# pcb_inverter.net
KiCad netlist of a schematic drawn in EAGLE
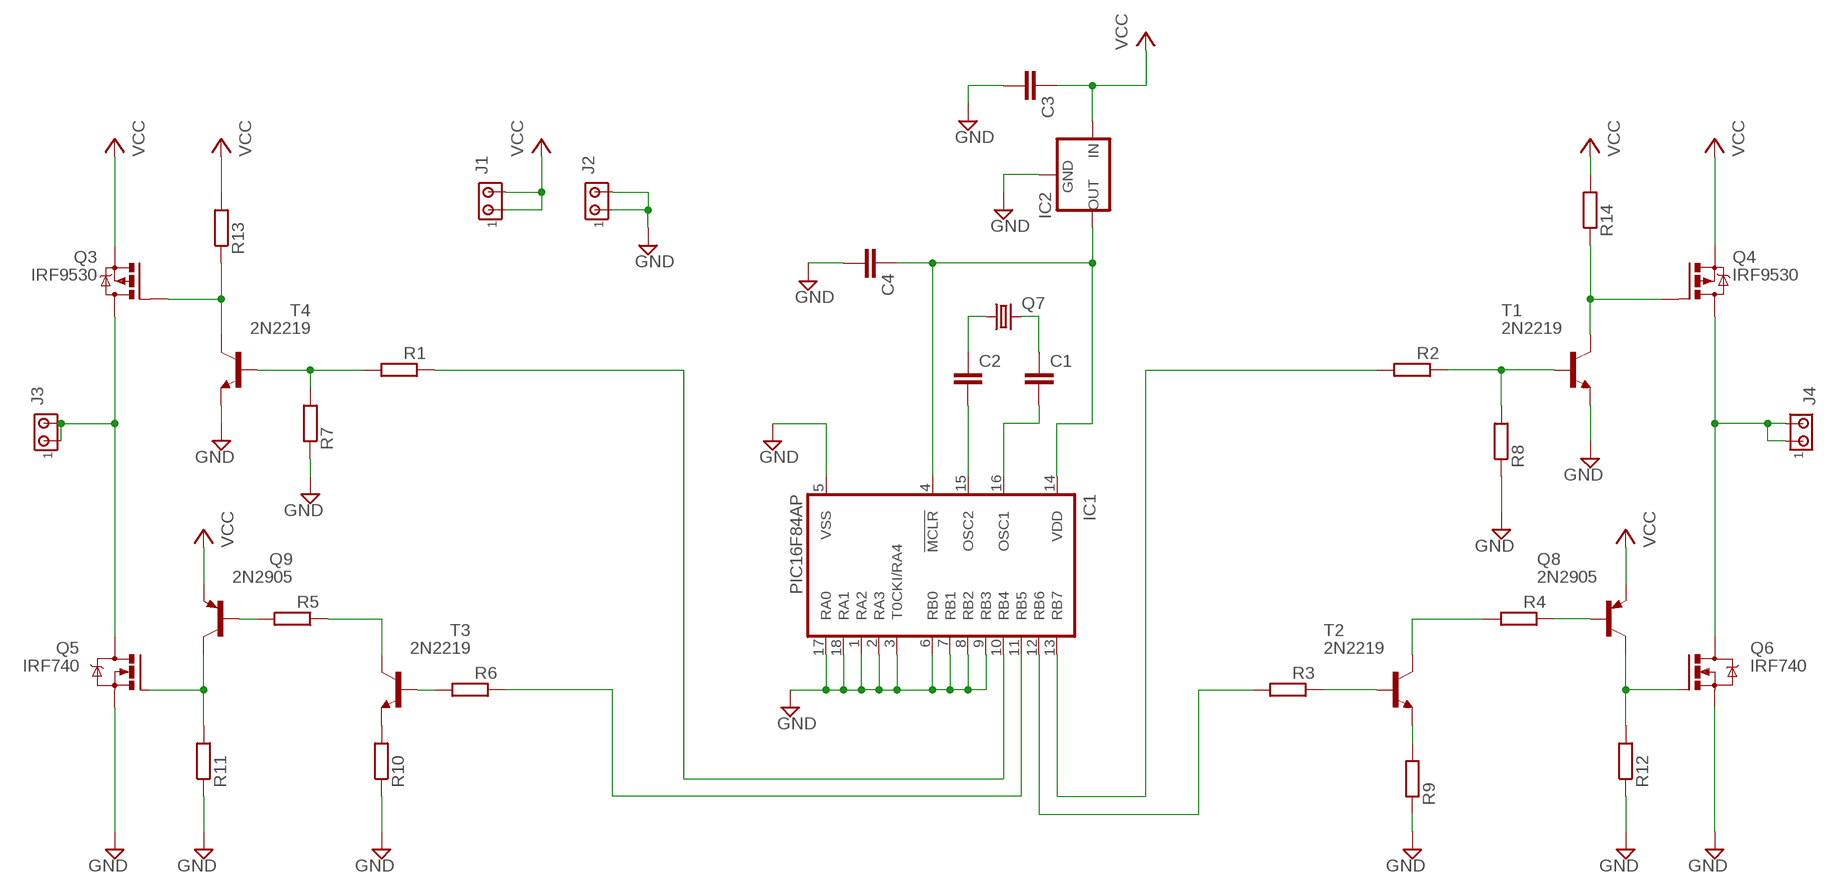
[diagram p0: schematic, sheet 1]

(export (version "E")
  (design (tool "Eeschema 10.0.6"))
  (components
    (comp (ref "C1")
      (value "C2.5/5")
      (footprint "eagle-import:C2.5-5")
      (libsource (lib "eagle-import") (part "C2.5/5"))
    )
    (comp (ref "C2")
      (value "C2.5/5")
      (footprint "eagle-import:C2.5-5")
      (libsource (lib "eagle-import") (part "C2.5/5"))
    )
    (comp (ref "C3")
      (value "C2.5/5")
      (footprint "eagle-import:C2.5-5")
      (libsource (lib "eagle-import") (part "C2.5/5"))
    )
    (comp (ref "C4")
      (value "C2.5/5")
      (footprint "eagle-import:C2.5-5")
      (libsource (lib "eagle-import") (part "C2.5/5"))
    )
    (comp (ref "IC1")
      (value "PIC16F84AP")
      (footprint "eagle-import:DIL18")
      (fields (field (name "MF") "MICROCHIP") (field (name "MPN") "PIC16F84A-04I/P"))
      (libsource (lib "eagle-import") (part "PIC16F8P4A"))
    )
    (comp (ref "IC2")
      (value "78XXS")
      (footprint "eagle-import:78XXS")
      (libsource (lib "eagle-import") (part "78XXS"))
    )
    (comp (ref "J1")
      (value "MTA02-156")
      (footprint "eagle-import:1X2MTA")
      (libsource (lib "eagle-import") (part "MTA02-156"))
    )
    (comp (ref "J2")
      (value "MTA02-156")
      (footprint "eagle-import:1X2MTA")
      (libsource (lib "eagle-import") (part "MTA02-156"))
    )
    (comp (ref "J3")
      (value "MTA02-156")
      (footprint "eagle-import:1X2MTA")
      (libsource (lib "eagle-import") (part "MTA02-156"))
    )
    (comp (ref "J4")
      (value "MTA02-156")
      (footprint "eagle-import:1X2MTA")
      (libsource (lib "eagle-import") (part "MTA02-156"))
    )
    (comp (ref "Q3")
      (value "IRF9530")
      (footprint "eagle-import:TO220BV")
      (libsource (lib "eagle-import") (part "IRF9530"))
    )
    (comp (ref "Q4")
      (value "IRF9530")
      (footprint "eagle-import:TO220BV")
      (libsource (lib "eagle-import") (part "IRF9530"))
    )
    (comp (ref "Q5")
      (value "IRF740")
      (footprint "eagle-import:TO220BV")
      (libsource (lib "eagle-import") (part "IRF740"))
    )
    (comp (ref "Q6")
      (value "IRF740")
      (footprint "eagle-import:TO220BV")
      (libsource (lib "eagle-import") (part "IRF740"))
    )
    (comp (ref "Q7")
      (value "CRYSTALHC18U-V")
      (footprint "eagle-import:HC18U-V")
      (libsource (lib "eagle-import") (part "CRYSTALHC18U-V"))
    )
    (comp (ref "Q8")
      (value "2N2905")
      (footprint "eagle-import:TO5")
      (libsource (lib "eagle-import") (part "2N2905"))
    )
    (comp (ref "Q9")
      (value "2N2905")
      (footprint "eagle-import:TO5")
      (libsource (lib "eagle-import") (part "2N2905"))
    )
    (comp (ref "R1")
      (value "R-EU_0204/7")
      (footprint "eagle-import:0204_7")
      (libsource (lib "eagle-import") (part "R-EU_0204/7"))
    )
    (comp (ref "R2")
      (value "R-EU_0204/7")
      (footprint "eagle-import:0204_7")
      (libsource (lib "eagle-import") (part "R-EU_0204/7"))
    )
    (comp (ref "R3")
      (value "R-EU_0204/7")
      (footprint "eagle-import:0204_7")
      (libsource (lib "eagle-import") (part "R-EU_0204/7"))
    )
    (comp (ref "R4")
      (value "R-EU_0204/7")
      (footprint "eagle-import:0204_7")
      (libsource (lib "eagle-import") (part "R-EU_0204/7"))
    )
    (comp (ref "R5")
      (value "R-EU_0204/7")
      (footprint "eagle-import:0204_7")
      (libsource (lib "eagle-import") (part "R-EU_0204/7"))
    )
    (comp (ref "R6")
      (value "R-EU_0204/7")
      (footprint "eagle-import:0204_7")
      (libsource (lib "eagle-import") (part "R-EU_0204/7"))
    )
    (comp (ref "R7")
      (value "R-EU_0204/7")
      (footprint "eagle-import:0204_7")
      (libsource (lib "eagle-import") (part "R-EU_0204/7"))
    )
    (comp (ref "R8")
      (value "R-EU_0204/7")
      (footprint "eagle-import:0204_7")
      (libsource (lib "eagle-import") (part "R-EU_0204/7"))
    )
    (comp (ref "R9")
      (value "R-EU_0204/7")
      (footprint "eagle-import:0204_7")
      (libsource (lib "eagle-import") (part "R-EU_0204/7"))
    )
    (comp (ref "R10")
      (value "R-EU_0204/7")
      (footprint "eagle-import:0204_7")
      (libsource (lib "eagle-import") (part "R-EU_0204/7"))
    )
    (comp (ref "R11")
      (value "R-EU_0204/7")
      (footprint "eagle-import:0204_7")
      (libsource (lib "eagle-import") (part "R-EU_0204/7"))
    )
    (comp (ref "R12")
      (value "R-EU_0204/7")
      (footprint "eagle-import:0204_7")
      (libsource (lib "eagle-import") (part "R-EU_0204/7"))
    )
    (comp (ref "R13")
      (value "R-EU_0204/7")
      (footprint "eagle-import:0204_7")
      (libsource (lib "eagle-import") (part "R-EU_0204/7"))
    )
    (comp (ref "R14")
      (value "R-EU_0204/7")
      (footprint "eagle-import:0204_7")
      (libsource (lib "eagle-import") (part "R-EU_0204/7"))
    )
    (comp (ref "T1")
      (value "2N2219")
      (footprint "eagle-import:TO5")
      (libsource (lib "eagle-import") (part "2N2219"))
    )
    (comp (ref "T2")
      (value "2N2219")
      (footprint "eagle-import:TO5")
      (libsource (lib "eagle-import") (part "2N2219"))
    )
    (comp (ref "T3")
      (value "2N2219")
      (footprint "eagle-import:TO5")
      (libsource (lib "eagle-import") (part "2N2219"))
    )
    (comp (ref "T4")
      (value "2N2219")
      (footprint "eagle-import:TO5")
      (libsource (lib "eagle-import") (part "2N2219"))
    )
  )
  (nets
    (net (code "1") (name "GND") (class "Default")
      (node (ref "C3") (pin "2") (pinfunction "2_2") (pintype "passive"))
      (node (ref "C4") (pin "2") (pinfunction "2_2") (pintype "passive"))
      (node (ref "IC1") (pin "1") (pinfunction "RA2_1") (pintype "bidirectional"))
      (node (ref "IC1") (pin "17") (pinfunction "RA0_17") (pintype "bidirectional"))
      (node (ref "IC1") (pin "18") (pinfunction "RA1_18") (pintype "bidirectional"))
      (node (ref "IC1") (pin "2") (pinfunction "RA3_2") (pintype "bidirectional"))
      (node (ref "IC1") (pin "3") (pinfunction "T0CKI/RA4_3") (pintype "bidirectional"))
      (node (ref "IC1") (pin "5") (pinfunction "VSS_5") (pintype "power_in"))
      (node (ref "IC1") (pin "6") (pinfunction "RB0_6") (pintype "bidirectional"))
      (node (ref "IC1") (pin "7") (pinfunction "RB1_7") (pintype "bidirectional"))
      (node (ref "IC1") (pin "8") (pinfunction "RB2_8") (pintype "bidirectional"))
      (node (ref "IC1") (pin "9") (pinfunction "RB3_9") (pintype "bidirectional"))
      (node (ref "IC2") (pin "GND") (pinfunction "GND_GND") (pintype "input"))
      (node (ref "J2") (pin "1") (pinfunction "1_1") (pintype "passive"))
      (node (ref "J2") (pin "2") (pinfunction "2_2") (pintype "passive"))
      (node (ref "Q5") (pin "S") (pinfunction "S_S") (pintype "passive"))
      (node (ref "Q6") (pin "S") (pinfunction "S_S") (pintype "passive"))
      (node (ref "R10") (pin "1") (pinfunction "1_1") (pintype "passive"))
      (node (ref "R11") (pin "1") (pinfunction "1_1") (pintype "passive"))
      (node (ref "R12") (pin "1") (pinfunction "1_1") (pintype "passive"))
      (node (ref "R7") (pin "1") (pinfunction "1_1") (pintype "passive"))
      (node (ref "R8") (pin "1") (pinfunction "1_1") (pintype "passive"))
      (node (ref "R9") (pin "1") (pinfunction "1_1") (pintype "passive"))
      (node (ref "T1") (pin "1") (pinfunction "E_1") (pintype "passive"))
      (node (ref "T4") (pin "1") (pinfunction "E_1") (pintype "passive"))
    )
    (net (code "2") (name "Net-(C1-Pad1)") (class "Default")
      (node (ref "C1") (pin "1") (pinfunction "1_1") (pintype "passive"))
      (node (ref "Q7") (pin "2") (pinfunction "2_2") (pintype "passive"))
    )
    (net (code "3") (name "Net-(C2-Pad1)") (class "Default")
      (node (ref "C2") (pin "1") (pinfunction "1_1") (pintype "passive"))
      (node (ref "Q7") (pin "1") (pinfunction "1_1") (pintype "passive"))
    )
    (net (code "4") (name "Net-(IC1-OSC1)") (class "Default")
      (node (ref "C1") (pin "2") (pinfunction "2_2") (pintype "passive"))
      (node (ref "IC1") (pin "16") (pinfunction "OSC1_16") (pintype "input"))
    )
    (net (code "5") (name "Net-(IC1-OSC2)") (class "Default")
      (node (ref "C2") (pin "2") (pinfunction "2_2") (pintype "passive"))
      (node (ref "IC1") (pin "15") (pinfunction "OSC2_15") (pintype "output"))
    )
    (net (code "6") (name "Net-(IC1-RB4)") (class "Default")
      (node (ref "IC1") (pin "10") (pinfunction "RB4_10") (pintype "bidirectional"))
      (node (ref "R1") (pin "1") (pinfunction "1_1") (pintype "passive"))
    )
    (net (code "7") (name "Net-(IC1-RB5)") (class "Default")
      (node (ref "IC1") (pin "11") (pinfunction "RB5_11") (pintype "bidirectional"))
      (node (ref "R6") (pin "1") (pinfunction "1_1") (pintype "passive"))
    )
    (net (code "8") (name "Net-(IC1-RB6)") (class "Default")
      (node (ref "IC1") (pin "12") (pinfunction "RB6_12") (pintype "bidirectional"))
      (node (ref "R3") (pin "2") (pinfunction "2_2") (pintype "passive"))
    )
    (net (code "9") (name "Net-(IC1-RB7)") (class "Default")
      (node (ref "IC1") (pin "13") (pinfunction "RB7_13") (pintype "bidirectional"))
      (node (ref "R2") (pin "2") (pinfunction "2_2") (pintype "passive"))
    )
    (net (code "10") (name "Net-(IC1-VDD)") (class "Default")
      (node (ref "C4") (pin "1") (pinfunction "1_1") (pintype "passive"))
      (node (ref "IC1") (pin "14") (pinfunction "VDD_14") (pintype "power_in"))
      (node (ref "IC1") (pin "4") (pinfunction "~{MCLR}_4") (pintype "input"))
      (node (ref "IC2") (pin "OUT") (pinfunction "OUT_OUT") (pintype "passive"))
    )
    (net (code "11") (name "Net-(J3-Pad1)") (class "Default")
      (node (ref "J3") (pin "1") (pinfunction "1_1") (pintype "passive"))
      (node (ref "J3") (pin "2") (pinfunction "2_2") (pintype "passive"))
      (node (ref "Q3") (pin "D") (pinfunction "D_D") (pintype "passive"))
      (node (ref "Q5") (pin "D") (pinfunction "D_D") (pintype "passive"))
    )
    (net (code "12") (name "Net-(J4-Pad1)") (class "Default")
      (node (ref "J4") (pin "1") (pinfunction "1_1") (pintype "passive"))
      (node (ref "J4") (pin "2") (pinfunction "2_2") (pintype "passive"))
      (node (ref "Q4") (pin "D") (pinfunction "D_D") (pintype "passive"))
      (node (ref "Q6") (pin "D") (pinfunction "D_D") (pintype "passive"))
    )
    (net (code "13") (name "Net-(Q8-B)") (class "Default")
      (node (ref "Q8") (pin "2") (pinfunction "B_2") (pintype "passive"))
      (node (ref "R4") (pin "1") (pinfunction "1_1") (pintype "passive"))
    )
    (net (code "14") (name "Net-(Q8-C)") (class "Default")
      (node (ref "Q6") (pin "G") (pinfunction "G_G") (pintype "passive"))
      (node (ref "Q8") (pin "3") (pinfunction "C_3") (pintype "passive"))
      (node (ref "R12") (pin "2") (pinfunction "2_2") (pintype "passive"))
    )
    (net (code "15") (name "Net-(Q9-B)") (class "Default")
      (node (ref "Q9") (pin "2") (pinfunction "B_2") (pintype "passive"))
      (node (ref "R5") (pin "2") (pinfunction "2_2") (pintype "passive"))
    )
    (net (code "16") (name "Net-(Q9-C)") (class "Default")
      (node (ref "Q5") (pin "G") (pinfunction "G_G") (pintype "passive"))
      (node (ref "Q9") (pin "3") (pinfunction "C_3") (pintype "passive"))
      (node (ref "R11") (pin "2") (pinfunction "2_2") (pintype "passive"))
    )
    (net (code "17") (name "Net-(T1-B)") (class "Default")
      (node (ref "R2") (pin "1") (pinfunction "1_1") (pintype "passive"))
      (node (ref "R8") (pin "2") (pinfunction "2_2") (pintype "passive"))
      (node (ref "T1") (pin "2") (pinfunction "B_2") (pintype "passive"))
    )
    (net (code "18") (name "Net-(T1-C)") (class "Default")
      (node (ref "Q4") (pin "G") (pinfunction "G_G") (pintype "passive"))
      (node (ref "R14") (pin "1") (pinfunction "1_1") (pintype "passive"))
      (node (ref "T1") (pin "3") (pinfunction "C_3") (pintype "passive"))
    )
    (net (code "19") (name "Net-(T2-B)") (class "Default")
      (node (ref "R3") (pin "1") (pinfunction "1_1") (pintype "passive"))
      (node (ref "T2") (pin "2") (pinfunction "B_2") (pintype "passive"))
    )
    (net (code "20") (name "Net-(T2-C)") (class "Default")
      (node (ref "R4") (pin "2") (pinfunction "2_2") (pintype "passive"))
      (node (ref "T2") (pin "3") (pinfunction "C_3") (pintype "passive"))
    )
    (net (code "21") (name "Net-(T2-E)") (class "Default")
      (node (ref "R9") (pin "2") (pinfunction "2_2") (pintype "passive"))
      (node (ref "T2") (pin "1") (pinfunction "E_1") (pintype "passive"))
    )
    (net (code "22") (name "Net-(T3-B)") (class "Default")
      (node (ref "R6") (pin "2") (pinfunction "2_2") (pintype "passive"))
      (node (ref "T3") (pin "2") (pinfunction "B_2") (pintype "passive"))
    )
    (net (code "23") (name "Net-(T3-C)") (class "Default")
      (node (ref "R5") (pin "1") (pinfunction "1_1") (pintype "passive"))
      (node (ref "T3") (pin "3") (pinfunction "C_3") (pintype "passive"))
    )
    (net (code "24") (name "Net-(T3-E)") (class "Default")
      (node (ref "R10") (pin "2") (pinfunction "2_2") (pintype "passive"))
      (node (ref "T3") (pin "1") (pinfunction "E_1") (pintype "passive"))
    )
    (net (code "25") (name "Net-(T4-B)") (class "Default")
      (node (ref "R1") (pin "2") (pinfunction "2_2") (pintype "passive"))
      (node (ref "R7") (pin "2") (pinfunction "2_2") (pintype "passive"))
      (node (ref "T4") (pin "2") (pinfunction "B_2") (pintype "passive"))
    )
    (net (code "26") (name "Net-(T4-C)") (class "Default")
      (node (ref "Q3") (pin "G") (pinfunction "G_G") (pintype "passive"))
      (node (ref "R13") (pin "1") (pinfunction "1_1") (pintype "passive"))
      (node (ref "T4") (pin "3") (pinfunction "C_3") (pintype "passive"))
    )
    (net (code "27") (name "VCC") (class "Default")
      (node (ref "C3") (pin "1") (pinfunction "1_1") (pintype "passive"))
      (node (ref "IC2") (pin "IN") (pinfunction "IN_IN") (pintype "input"))
      (node (ref "J1") (pin "1") (pinfunction "1_1") (pintype "passive"))
      (node (ref "J1") (pin "2") (pinfunction "2_2") (pintype "passive"))
      (node (ref "Q3") (pin "S") (pinfunction "S_S") (pintype "passive"))
      (node (ref "Q4") (pin "S") (pinfunction "S_S") (pintype "passive"))
      (node (ref "Q8") (pin "1") (pinfunction "E_1") (pintype "passive"))
      (node (ref "Q9") (pin "1") (pinfunction "E_1") (pintype "passive"))
      (node (ref "R13") (pin "2") (pinfunction "2_2") (pintype "passive"))
      (node (ref "R14") (pin "2") (pinfunction "2_2") (pintype "passive"))
    )
  )
)
